# wb_SMD.net
KiCad netlist of a schematic drawn in EAGLE
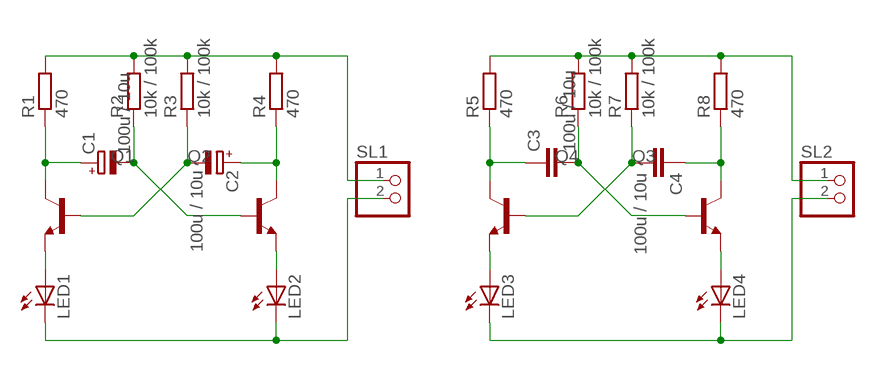
[diagram p0: schematic, sheet 1]

(export (version "E")
  (design (tool "Eeschema 10.0.6"))
  (components
    (comp (ref "C1")
      (value "100u / 10u")
      (footprint "eagle-import:PANASONIC_B")
      (libsource (lib "eagle-import") (part "CPOL-EUB"))
    )
    (comp (ref "C2")
      (value "100u / 10u")
      (footprint "eagle-import:PANASONIC_B")
      (libsource (lib "eagle-import") (part "CPOL-EUB"))
    )
    (comp (ref "C3")
      (value "100u / 10u")
      (footprint "eagle-import:C0805K")
      (libsource (lib "eagle-import") (part "C-EUC0805K"))
    )
    (comp (ref "C4")
      (value "100u / 10u")
      (footprint "eagle-import:C0805K")
      (libsource (lib "eagle-import") (part "C-EUC0805K"))
    )
    (comp (ref "LED1")
      (value "LEDSML0805")
      (footprint "eagle-import:SML0805")
      (libsource (lib "eagle-import") (part "LEDSML0805"))
    )
    (comp (ref "LED2")
      (value "LEDSML0805")
      (footprint "eagle-import:SML0805")
      (libsource (lib "eagle-import") (part "LEDSML0805"))
    )
    (comp (ref "LED3")
      (value "LEDSML0805")
      (footprint "eagle-import:SML0805")
      (libsource (lib "eagle-import") (part "LEDSML0805"))
    )
    (comp (ref "LED4")
      (value "LEDSML0805")
      (footprint "eagle-import:SML0805")
      (libsource (lib "eagle-import") (part "LEDSML0805"))
    )
    (comp (ref "Q1")
      (value "BC817-25-NPN-SOT23-BEC")
      (footprint "eagle-import:SOT23-BEC")
      (libsource (lib "eagle-import") (part "-NPN-SOT23-BECBC817-25"))
    )
    (comp (ref "Q2")
      (value "BC817-25-NPN-SOT23-BEC")
      (footprint "eagle-import:SOT23-BEC")
      (libsource (lib "eagle-import") (part "-NPN-SOT23-BECBC817-25"))
    )
    (comp (ref "Q3")
      (value "BC817-25-NPN-SOT23-BEC")
      (footprint "eagle-import:SOT23-BEC")
      (libsource (lib "eagle-import") (part "-NPN-SOT23-BECBC817-25"))
    )
    (comp (ref "Q4")
      (value "BC817-25-NPN-SOT23-BEC")
      (footprint "eagle-import:SOT23-BEC")
      (libsource (lib "eagle-import") (part "-NPN-SOT23-BECBC817-25"))
    )
    (comp (ref "R1")
      (value "470")
      (footprint "eagle-import:M1206")
      (libsource (lib "eagle-import") (part "R-EU_M1206"))
    )
    (comp (ref "R2")
      (value "10k / 100k")
      (footprint "eagle-import:M1206")
      (libsource (lib "eagle-import") (part "R-EU_M1206"))
    )
    (comp (ref "R3")
      (value "10k / 100k")
      (footprint "eagle-import:M1206")
      (libsource (lib "eagle-import") (part "R-EU_M1206"))
    )
    (comp (ref "R4")
      (value "470")
      (footprint "eagle-import:M1206")
      (libsource (lib "eagle-import") (part "R-EU_M1206"))
    )
    (comp (ref "R5")
      (value "470")
      (footprint "eagle-import:M1206")
      (libsource (lib "eagle-import") (part "R-EU_M1206"))
    )
    (comp (ref "R6")
      (value "10k / 100k")
      (footprint "eagle-import:M1206")
      (libsource (lib "eagle-import") (part "R-EU_M1206"))
    )
    (comp (ref "R7")
      (value "10k / 100k")
      (footprint "eagle-import:M1206")
      (libsource (lib "eagle-import") (part "R-EU_M1206"))
    )
    (comp (ref "R8")
      (value "470")
      (footprint "eagle-import:M1206")
      (libsource (lib "eagle-import") (part "R-EU_M1206"))
    )
    (comp (ref "SL1")
      (value "PINHD-1X2")
      (footprint "eagle-import:1X02")
      (libsource (lib "eagle-import") (part "PINHD-1X2"))
    )
    (comp (ref "SL2")
      (value "PINHD-1X2")
      (footprint "eagle-import:1X02")
      (libsource (lib "eagle-import") (part "PINHD-1X2"))
    )
  )
  (nets
    (net (code "1") (name "Net-(C1-Pad+)") (class "Default")
      (node (ref "C1") (pin "+") (pinfunction "+_+") (pintype "passive"))
      (node (ref "Q1") (pin "C") (pinfunction "C_C") (pintype "passive"))
      (node (ref "R1") (pin "1") (pinfunction "1_1") (pintype "passive"))
    )
    (net (code "2") (name "Net-(C1-Pad-)") (class "Default")
      (node (ref "C1") (pin "-") (pinfunction "-_-") (pintype "passive"))
      (node (ref "Q2") (pin "B") (pinfunction "B_B") (pintype "passive"))
      (node (ref "R2") (pin "1") (pinfunction "1_1") (pintype "passive"))
    )
    (net (code "3") (name "Net-(C2-Pad+)") (class "Default")
      (node (ref "C2") (pin "+") (pinfunction "+_+") (pintype "passive"))
      (node (ref "Q2") (pin "C") (pinfunction "C_C") (pintype "passive"))
      (node (ref "R4") (pin "1") (pinfunction "1_1") (pintype "passive"))
    )
    (net (code "4") (name "Net-(C2-Pad-)") (class "Default")
      (node (ref "C2") (pin "-") (pinfunction "-_-") (pintype "passive"))
      (node (ref "Q1") (pin "B") (pinfunction "B_B") (pintype "passive"))
      (node (ref "R3") (pin "1") (pinfunction "1_1") (pintype "passive"))
    )
    (net (code "5") (name "Net-(C3-Pad1)") (class "Default")
      (node (ref "C3") (pin "1") (pinfunction "1_1") (pintype "passive"))
      (node (ref "Q4") (pin "C") (pinfunction "C_C") (pintype "passive"))
      (node (ref "R5") (pin "1") (pinfunction "1_1") (pintype "passive"))
    )
    (net (code "6") (name "Net-(C3-Pad2)") (class "Default")
      (node (ref "C3") (pin "2") (pinfunction "2_2") (pintype "passive"))
      (node (ref "Q3") (pin "B") (pinfunction "B_B") (pintype "passive"))
      (node (ref "R6") (pin "1") (pinfunction "1_1") (pintype "passive"))
    )
    (net (code "7") (name "Net-(C4-Pad1)") (class "Default")
      (node (ref "C4") (pin "1") (pinfunction "1_1") (pintype "passive"))
      (node (ref "Q3") (pin "C") (pinfunction "C_C") (pintype "passive"))
      (node (ref "R8") (pin "1") (pinfunction "1_1") (pintype "passive"))
    )
    (net (code "8") (name "Net-(C4-Pad2)") (class "Default")
      (node (ref "C4") (pin "2") (pinfunction "2_2") (pintype "passive"))
      (node (ref "Q4") (pin "B") (pinfunction "B_B") (pintype "passive"))
      (node (ref "R7") (pin "1") (pinfunction "1_1") (pintype "passive"))
    )
    (net (code "9") (name "Net-(LED1-PadA)") (class "Default")
      (node (ref "LED1") (pin "A") (pinfunction "A_A") (pintype "passive"))
      (node (ref "Q1") (pin "E") (pinfunction "E_E") (pintype "passive"))
    )
    (net (code "10") (name "Net-(LED1-PadC)") (class "Default")
      (node (ref "LED1") (pin "C") (pinfunction "C_C") (pintype "passive"))
      (node (ref "LED2") (pin "C") (pinfunction "C_C") (pintype "passive"))
      (node (ref "SL1") (pin "2") (pinfunction "2_2") (pintype "passive"))
    )
    (net (code "11") (name "Net-(LED2-PadA)") (class "Default")
      (node (ref "LED2") (pin "A") (pinfunction "A_A") (pintype "passive"))
      (node (ref "Q2") (pin "E") (pinfunction "E_E") (pintype "passive"))
    )
    (net (code "12") (name "Net-(LED3-PadA)") (class "Default")
      (node (ref "LED3") (pin "A") (pinfunction "A_A") (pintype "passive"))
      (node (ref "Q4") (pin "E") (pinfunction "E_E") (pintype "passive"))
    )
    (net (code "13") (name "Net-(LED3-PadC)") (class "Default")
      (node (ref "LED3") (pin "C") (pinfunction "C_C") (pintype "passive"))
      (node (ref "LED4") (pin "C") (pinfunction "C_C") (pintype "passive"))
      (node (ref "SL2") (pin "2") (pinfunction "2_2") (pintype "passive"))
    )
    (net (code "14") (name "Net-(LED4-PadA)") (class "Default")
      (node (ref "LED4") (pin "A") (pinfunction "A_A") (pintype "passive"))
      (node (ref "Q3") (pin "E") (pinfunction "E_E") (pintype "passive"))
    )
    (net (code "15") (name "Net-(R1-Pad2)") (class "Default")
      (node (ref "R1") (pin "2") (pinfunction "2_2") (pintype "passive"))
      (node (ref "R2") (pin "2") (pinfunction "2_2") (pintype "passive"))
      (node (ref "R3") (pin "2") (pinfunction "2_2") (pintype "passive"))
      (node (ref "R4") (pin "2") (pinfunction "2_2") (pintype "passive"))
      (node (ref "SL1") (pin "1") (pinfunction "1_1") (pintype "passive"))
    )
    (net (code "16") (name "Net-(R5-Pad2)") (class "Default")
      (node (ref "R5") (pin "2") (pinfunction "2_2") (pintype "passive"))
      (node (ref "R6") (pin "2") (pinfunction "2_2") (pintype "passive"))
      (node (ref "R7") (pin "2") (pinfunction "2_2") (pintype "passive"))
      (node (ref "R8") (pin "2") (pinfunction "2_2") (pintype "passive"))
      (node (ref "SL2") (pin "1") (pinfunction "1_1") (pintype "passive"))
    )
  )
)
